# EEPROM.net
KiCad netlist of a schematic drawn in Altium Designer
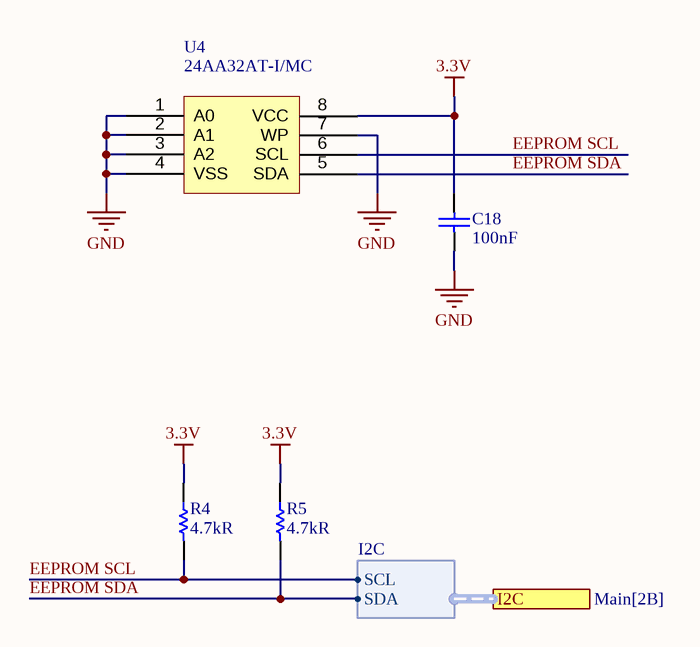
[diagram p0: EEPROM.SchDoc]

(export (version "E")
  (design (tool "Eeschema 10.0.6"))
  (components
    (comp (ref "C18")
      (value "100nF")
      (footprint "Capacitor 0402")
      (libsource (lib "x-io") (part "Capacitor"))
    )
    (comp (ref "R4") (value "4.7kR") (footprint "Resistor 0402") (libsource (lib "x-io") (part "Resistor")))
    (comp (ref "R5") (value "4.7kR") (footprint "Resistor 0402") (libsource (lib "x-io") (part "Resistor")))
    (comp (ref "U4")
      (value "24AA32AT-I/MC")
      (footprint "TDFN-8 2x3mm")
      (libsource (lib "x-io") (part "24AA32A"))
    )
  )
  (nets
    (net (code "2") (name "/EEPROM SCL") (class "Default")
      (node (ref "R4") (pin "1") (pinfunction "1_1") (pintype "passive"))
      (node (ref "U4") (pin "6") (pinfunction "SCL_6") (pintype "passive"))
    )
    (net (code "3") (name "/EEPROM SDA") (class "Default")
      (node (ref "R5") (pin "1") (pinfunction "1_1") (pintype "passive"))
      (node (ref "U4") (pin "5") (pinfunction "SDA_5") (pintype "passive"))
    )
    (net (code "5") (name "3.3V") (class "Default")
      (node (ref "C18") (pin "2") (pinfunction "2_2") (pintype "passive"))
      (node (ref "R4") (pin "2") (pinfunction "2_2") (pintype "passive"))
      (node (ref "R5") (pin "2") (pinfunction "2_2") (pintype "passive"))
      (node (ref "U4") (pin "8") (pinfunction "VCC_8") (pintype "passive"))
    )
    (net (code "6") (name "GND") (class "Default")
      (node (ref "C18") (pin "1") (pinfunction "1_1") (pintype "passive"))
      (node (ref "U4") (pin "1") (pinfunction "A0_1") (pintype "passive"))
      (node (ref "U4") (pin "2") (pinfunction "A1_2") (pintype "passive"))
      (node (ref "U4") (pin "3") (pinfunction "A2_3") (pintype "passive"))
      (node (ref "U4") (pin "4") (pinfunction "VSS_4") (pintype "passive"))
      (node (ref "U4") (pin "7") (pinfunction "WP_7") (pintype "passive"))
    )
  )
)
